# DW1000.net
KiCad netlist of a schematic drawn in Altium Designer
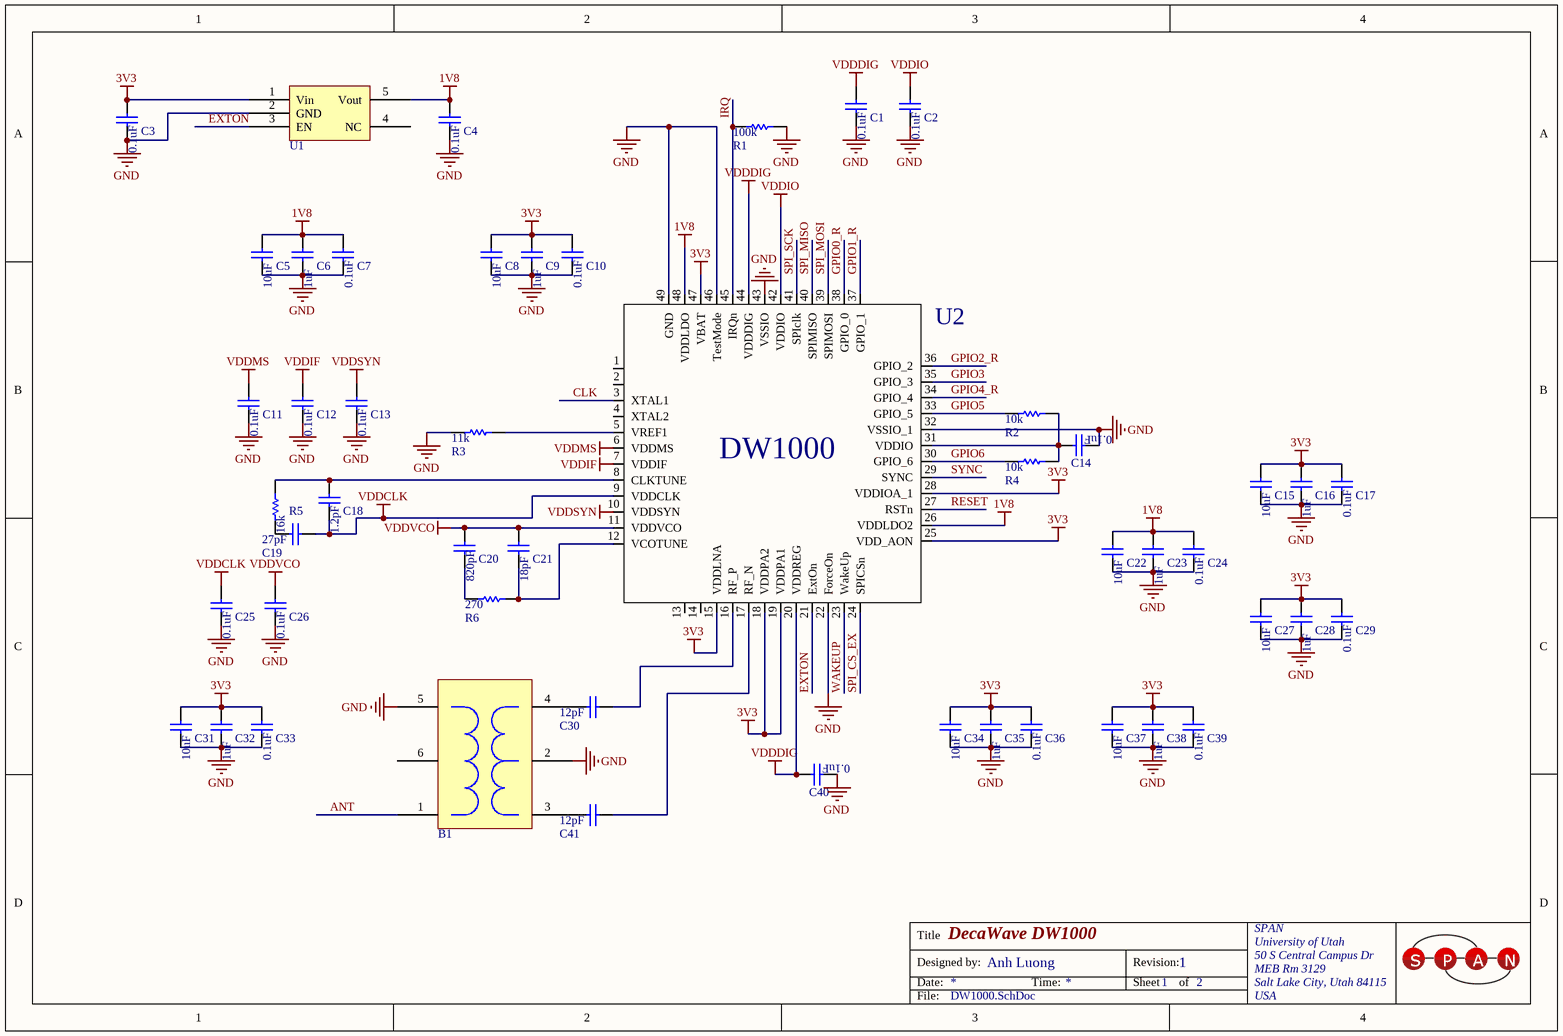
[diagram p0: DW1000.SchDoc]

(export (version "E")
  (design (tool "Eeschema 10.0.6"))
  (components
    (comp (ref "B1")
      (value "HHM1595A1")
      (footprint "BALUN")
      (description "XFMR BALUN RF 3.0-8.0GHZ UWB SMD")
      (fields (field (name "MANUFACTURER") "TDK Corporation"))
      (libsource (lib "DW1000Breakout") (part "HHM1595A1"))
    )
    (comp (ref "C1")
      (value "GRM188R71C104KA01D")
      (footprint "CAPC1608X08N (0603)")
      (description "CAP CER 0.1UF 16V 10% X7R 0603")
      (fields
        (field (name "MANUFACTURER") "Murata Electronics North America")
        (field (name "TOLERANCE") "±10%")
      )
      (libsource (lib "DW1000Breakout") (part "GRM188R71C104KA01D"))
    )
    (comp (ref "C2")
      (value "GRM188R71C104KA01D")
      (footprint "CAPC1608X08N (0603)")
      (description "CAP CER 0.1UF 16V 10% X7R 0603")
      (fields
        (field (name "MANUFACTURER") "Murata Electronics North America")
        (field (name "TOLERANCE") "±10%")
      )
      (libsource (lib "DW1000Breakout") (part "GRM188R71C104KA01D"))
    )
    (comp (ref "C3")
      (value "GRM188R71C104KA01D")
      (footprint "CAPC1608X08N (0603)")
      (description "CAP CER 0.1UF 16V 10% X7R 0603")
      (fields
        (field (name "MANUFACTURER") "Murata Electronics North America")
        (field (name "TOLERANCE") "±10%")
      )
      (libsource (lib "DW1000Breakout") (part "GRM188R71C104KA01D"))
    )
    (comp (ref "C4")
      (value "GRM188R71C104KA01D")
      (footprint "CAPC1608X08N (0603)")
      (description "CAP CER 0.1UF 16V 10% X7R 0603")
      (fields
        (field (name "MANUFACTURER") "Murata Electronics North America")
        (field (name "TOLERANCE") "±10%")
      )
      (libsource (lib "DW1000Breakout") (part "GRM188R71C104KA01D"))
    )
    (comp (ref "C5")
      (value "GRM188R60J106ME47D")
      (footprint "CAPC1608X08N (0603)")
      (description "CAP CER 10UF 6.3V 20% X5R 0603")
      (fields
        (field (name "MANUFACTURER") "Murata Electronics North America")
        (field (name "TOLERANCE") "±20%")
      )
      (libsource (lib "DWM1000Breakout") (part "GRM188R60J106ME47D"))
    )
    (comp (ref "C6")
      (value "GRM188R61A105KA61D")
      (footprint "CAPC1608X08N (0603)")
      (description "CAP CER 1UF 10V 10% X5R 0603")
      (fields
        (field (name "MANUFACTURER") "Murata Electronics North America")
        (field (name "TOLERANCE") "±10%")
      )
      (libsource (lib "DWM1000Breakout") (part "GRM188R61A105KA61D"))
    )
    (comp (ref "C7")
      (value "GRM188R71C104KA01D")
      (footprint "CAPC1608X08N (0603)")
      (description "CAP CER 0.1UF 16V 10% X7R 0603")
      (fields
        (field (name "MANUFACTURER") "Murata Electronics North America")
        (field (name "TOLERANCE") "±10%")
      )
      (libsource (lib "DWM1000Breakout") (part "GRM188R71C104KA01D"))
    )
    (comp (ref "C8")
      (value "GRM188R60J106ME47D")
      (footprint "CAPC1608X08N (0603)")
      (description "CAP CER 10UF 6.3V 20% X5R 0603")
      (fields
        (field (name "MANUFACTURER") "Murata Electronics North America")
        (field (name "TOLERANCE") "±20%")
      )
      (libsource (lib "DWM1000Breakout") (part "GRM188R60J106ME47D"))
    )
    (comp (ref "C9")
      (value "GRM188R61A105KA61D")
      (footprint "CAPC1608X08N (0603)")
      (description "CAP CER 1UF 10V 10% X5R 0603")
      (fields
        (field (name "MANUFACTURER") "Murata Electronics North America")
        (field (name "TOLERANCE") "±10%")
      )
      (libsource (lib "DWM1000Breakout") (part "GRM188R61A105KA61D"))
    )
    (comp (ref "C10")
      (value "GRM188R71C104KA01D")
      (footprint "CAPC1608X08N (0603)")
      (description "CAP CER 0.1UF 16V 10% X7R 0603")
      (fields
        (field (name "MANUFACTURER") "Murata Electronics North America")
        (field (name "TOLERANCE") "±10%")
      )
      (libsource (lib "DWM1000Breakout") (part "GRM188R71C104KA01D"))
    )
    (comp (ref "C11")
      (value "GRM188R71C104KA01D")
      (footprint "CAPC1608X08N (0603)")
      (description "CAP CER 0.1UF 16V 10% X7R 0603")
      (fields
        (field (name "MANUFACTURER") "Murata Electronics North America")
        (field (name "TOLERANCE") "±10%")
      )
      (libsource (lib "DW1000Breakout") (part "GRM188R71C104KA01D"))
    )
    (comp (ref "C12")
      (value "GRM188R71C104KA01D")
      (footprint "CAPC1608X08N (0603)")
      (description "CAP CER 0.1UF 16V 10% X7R 0603")
      (fields
        (field (name "MANUFACTURER") "Murata Electronics North America")
        (field (name "TOLERANCE") "±10%")
      )
      (libsource (lib "DW1000Breakout") (part "GRM188R71C104KA01D"))
    )
    (comp (ref "C13")
      (value "GRM188R71C104KA01D")
      (footprint "CAPC1608X08N (0603)")
      (description "CAP CER 0.1UF 16V 10% X7R 0603")
      (fields
        (field (name "MANUFACTURER") "Murata Electronics North America")
        (field (name "TOLERANCE") "±10%")
      )
      (libsource (lib "DW1000Breakout") (part "GRM188R71C104KA01D"))
    )
    (comp (ref "C14")
      (value "GRM188R71C104KA01D")
      (footprint "CAPC1608X08N (0603)")
      (description "CAP CER 0.1UF 16V 10% X7R 0603")
      (fields
        (field (name "MANUFACTURER") "Murata Electronics North America")
        (field (name "TOLERANCE") "±10%")
      )
      (libsource (lib "DW1000Breakout") (part "GRM188R71C104KA01D"))
    )
    (comp (ref "C15")
      (value "GRM188R60J106ME47D")
      (footprint "CAPC1608X08N (0603)")
      (description "CAP CER 10UF 6.3V 20% X5R 0603")
      (fields
        (field (name "MANUFACTURER") "Murata Electronics North America")
        (field (name "TOLERANCE") "±20%")
      )
      (libsource (lib "DWM1000Breakout") (part "GRM188R60J106ME47D"))
    )
    (comp (ref "C16")
      (value "GRM188R61A105KA61D")
      (footprint "CAPC1608X08N (0603)")
      (description "CAP CER 1UF 10V 10% X5R 0603")
      (fields
        (field (name "MANUFACTURER") "Murata Electronics North America")
        (field (name "TOLERANCE") "±10%")
      )
      (libsource (lib "DWM1000Breakout") (part "GRM188R61A105KA61D"))
    )
    (comp (ref "C17")
      (value "GRM188R71C104KA01D")
      (footprint "CAPC1608X08N (0603)")
      (description "CAP CER 0.1UF 16V 10% X7R 0603")
      (fields
        (field (name "MANUFACTURER") "Murata Electronics North America")
        (field (name "TOLERANCE") "±10%")
      )
      (libsource (lib "DWM1000Breakout") (part "GRM188R71C104KA01D"))
    )
    (comp (ref "C18")
      (value "GRM1885C1H1R2CA01D")
      (footprint "CAPC1608X08N (0603)")
      (description "CAP CER 1.2PF 50V NP0 0603")
      (fields
        (field (name "MANUFACTURER") "Murata Electronics North America")
        (field (name "TOLERANCE") "±0.25pF")
      )
      (libsource (lib "DW1000Breakout") (part "GRM1885C1H1R2CA01D"))
    )
    (comp (ref "C19")
      (value "GRM1885C1H270JA01D")
      (footprint "CAPC1608X08N (0603)")
      (description "CAP CER 27PF 50V NP0 0603")
      (fields
        (field (name "MANUFACTURER") "Murata Electronics North America")
        (field (name "TOLERANCE") "±5%")
      )
      (libsource (lib "DW1000Breakout") (part "GRM1885C1H270JA01D"))
    )
    (comp (ref "C20")
      (value "GRM188R71H821KA01D")
      (footprint "CAPC1608X08N (0603)")
      (description "CAP CER 820PF 50V X7R 0603")
      (fields
        (field (name "MANUFACTURER") "Murata Electronics North America")
        (field (name "TOLERANCE") "±10%")
      )
      (libsource (lib "DW1000Breakout") (part "GRM188R71H821KA01D"))
    )
    (comp (ref "C21")
      (value "GRM1885C1H180JA01D")
      (footprint "CAPC1608X08N (0603)")
      (description "CAP CER 18PF 50V NP0 0603")
      (fields
        (field (name "MANUFACTURER") "Murata Electronics North America")
        (field (name "TOLERANCE") "±5%")
      )
      (libsource (lib "DW1000Breakout") (part "GRM1885C1H180JA01D"))
    )
    (comp (ref "C22")
      (value "GRM188R60J106ME47D")
      (footprint "CAPC1608X08N (0603)")
      (description "CAP CER 10UF 6.3V 20% X5R 0603")
      (fields
        (field (name "MANUFACTURER") "Murata Electronics North America")
        (field (name "TOLERANCE") "±20%")
      )
      (libsource (lib "DWM1000Breakout") (part "GRM188R60J106ME47D"))
    )
    (comp (ref "C23")
      (value "GRM188R61A105KA61D")
      (footprint "CAPC1608X08N (0603)")
      (description "CAP CER 1UF 10V 10% X5R 0603")
      (fields
        (field (name "MANUFACTURER") "Murata Electronics North America")
        (field (name "TOLERANCE") "±10%")
      )
      (libsource (lib "DWM1000Breakout") (part "GRM188R61A105KA61D"))
    )
    (comp (ref "C24")
      (value "GRM188R71C104KA01D")
      (footprint "CAPC1608X08N (0603)")
      (description "CAP CER 0.1UF 16V 10% X7R 0603")
      (fields
        (field (name "MANUFACTURER") "Murata Electronics North America")
        (field (name "TOLERANCE") "±10%")
      )
      (libsource (lib "DWM1000Breakout") (part "GRM188R71C104KA01D"))
    )
    (comp (ref "C25")
      (value "GRM188R71C104KA01D")
      (footprint "CAPC1608X08N (0603)")
      (description "CAP CER 0.1UF 16V 10% X7R 0603")
      (fields
        (field (name "MANUFACTURER") "Murata Electronics North America")
        (field (name "TOLERANCE") "±10%")
      )
      (libsource (lib "DWM1000Breakout") (part "GRM188R71C104KA01D"))
    )
    (comp (ref "C26")
      (value "GRM188R71C104KA01D")
      (footprint "CAPC1608X08N (0603)")
      (description "CAP CER 0.1UF 16V 10% X7R 0603")
      (fields
        (field (name "MANUFACTURER") "Murata Electronics North America")
        (field (name "TOLERANCE") "±10%")
      )
      (libsource (lib "DWM1000Breakout") (part "GRM188R71C104KA01D"))
    )
    (comp (ref "C27")
      (value "GRM188R60J106ME47D")
      (footprint "CAPC1608X08N (0603)")
      (description "CAP CER 10UF 6.3V 20% X5R 0603")
      (fields
        (field (name "MANUFACTURER") "Murata Electronics North America")
        (field (name "TOLERANCE") "±20%")
      )
      (libsource (lib "DWM1000Breakout") (part "GRM188R60J106ME47D"))
    )
    (comp (ref "C28")
      (value "GRM188R61A105KA61D")
      (footprint "CAPC1608X08N (0603)")
      (description "CAP CER 1UF 10V 10% X5R 0603")
      (fields
        (field (name "MANUFACTURER") "Murata Electronics North America")
        (field (name "TOLERANCE") "±10%")
      )
      (libsource (lib "DWM1000Breakout") (part "GRM188R61A105KA61D"))
    )
    (comp (ref "C29")
      (value "GRM188R71C104KA01D")
      (footprint "CAPC1608X08N (0603)")
      (description "CAP CER 0.1UF 16V 10% X7R 0603")
      (fields
        (field (name "MANUFACTURER") "Murata Electronics North America")
        (field (name "TOLERANCE") "±10%")
      )
      (libsource (lib "DWM1000Breakout") (part "GRM188R71C104KA01D"))
    )
    (comp (ref "C30")
      (value "GRM1885C1H120JA01D")
      (footprint "CAPC1608X08N (0603)")
      (description "CAP CER 12PF 50V NP0 0603")
      (fields
        (field (name "MANUFACTURER") "Murata Electronics North America")
        (field (name "TOLERANCE") "±5%")
      )
      (libsource (lib "DW1000Breakout") (part "GRM1885C1H120JA01D"))
    )
    (comp (ref "C31")
      (value "GRM188R60J106ME47D")
      (footprint "CAPC1608X08N (0603)")
      (description "CAP CER 10UF 6.3V 20% X5R 0603")
      (fields
        (field (name "MANUFACTURER") "Murata Electronics North America")
        (field (name "TOLERANCE") "±20%")
      )
      (libsource (lib "DWM1000Breakout") (part "GRM188R60J106ME47D"))
    )
    (comp (ref "C32")
      (value "GRM188R61A105KA61D")
      (footprint "CAPC1608X08N (0603)")
      (description "CAP CER 1UF 10V 10% X5R 0603")
      (fields
        (field (name "MANUFACTURER") "Murata Electronics North America")
        (field (name "TOLERANCE") "±10%")
      )
      (libsource (lib "DWM1000Breakout") (part "GRM188R61A105KA61D"))
    )
    (comp (ref "C33")
      (value "GRM188R71C104KA01D")
      (footprint "CAPC1608X08N (0603)")
      (description "CAP CER 0.1UF 16V 10% X7R 0603")
      (fields
        (field (name "MANUFACTURER") "Murata Electronics North America")
        (field (name "TOLERANCE") "±10%")
      )
      (libsource (lib "DWM1000Breakout") (part "GRM188R71C104KA01D"))
    )
    (comp (ref "C34")
      (value "GRM188R60J106ME47D")
      (footprint "CAPC1608X08N (0603)")
      (description "CAP CER 10UF 6.3V 20% X5R 0603")
      (fields
        (field (name "MANUFACTURER") "Murata Electronics North America")
        (field (name "TOLERANCE") "±20%")
      )
      (libsource (lib "DWM1000Breakout") (part "GRM188R60J106ME47D"))
    )
    (comp (ref "C35")
      (value "GRM188R61A105KA61D")
      (footprint "CAPC1608X08N (0603)")
      (description "CAP CER 1UF 10V 10% X5R 0603")
      (fields
        (field (name "MANUFACTURER") "Murata Electronics North America")
        (field (name "TOLERANCE") "±10%")
      )
      (libsource (lib "DWM1000Breakout") (part "GRM188R61A105KA61D"))
    )
    (comp (ref "C36")
      (value "GRM188R71C104KA01D")
      (footprint "CAPC1608X08N (0603)")
      (description "CAP CER 0.1UF 16V 10% X7R 0603")
      (fields
        (field (name "MANUFACTURER") "Murata Electronics North America")
        (field (name "TOLERANCE") "±10%")
      )
      (libsource (lib "DWM1000Breakout") (part "GRM188R71C104KA01D"))
    )
    (comp (ref "C37")
      (value "GRM188R60J106ME47D")
      (footprint "CAPC1608X08N (0603)")
      (description "CAP CER 10UF 6.3V 20% X5R 0603")
      (fields
        (field (name "MANUFACTURER") "Murata Electronics North America")
        (field (name "TOLERANCE") "±20%")
      )
      (libsource (lib "DWM1000Breakout") (part "GRM188R60J106ME47D"))
    )
    (comp (ref "C38")
      (value "GRM188R61A105KA61D")
      (footprint "CAPC1608X08N (0603)")
      (description "CAP CER 1UF 10V 10% X5R 0603")
      (fields
        (field (name "MANUFACTURER") "Murata Electronics North America")
        (field (name "TOLERANCE") "±10%")
      )
      (libsource (lib "DWM1000Breakout") (part "GRM188R61A105KA61D"))
    )
    (comp (ref "C39")
      (value "GRM188R71C104KA01D")
      (footprint "CAPC1608X08N (0603)")
      (description "CAP CER 0.1UF 16V 10% X7R 0603")
      (fields
        (field (name "MANUFACTURER") "Murata Electronics North America")
        (field (name "TOLERANCE") "±10%")
      )
      (libsource (lib "DWM1000Breakout") (part "GRM188R71C104KA01D"))
    )
    (comp (ref "C40")
      (value "GRM188R71C104KA01D")
      (footprint "CAPC1608X08N (0603)")
      (description "CAP CER 0.1UF 16V 10% X7R 0603")
      (fields
        (field (name "MANUFACTURER") "Murata Electronics North America")
        (field (name "TOLERANCE") "±10%")
      )
      (libsource (lib "DW1000Breakout") (part "GRM188R71C104KA01D"))
    )
    (comp (ref "C41")
      (value "GRM1885C1H120JA01D")
      (footprint "CAPC1608X08N (0603)")
      (description "CAP CER 12PF 50V NP0 0603")
      (fields
        (field (name "MANUFACTURER") "Murata Electronics North America")
        (field (name "TOLERANCE") "±5%")
      )
      (libsource (lib "DW1000Breakout") (part "GRM1885C1H120JA01D"))
    )
    (comp (ref "R1")
      (value "MCR03ERTJ104")
      (footprint "RESC1608X06N (0603)")
      (description "RES SMD 100K OHM 5% 1/10W 0603")
      (fields (field (name "MANUFACTURER") "Rohm Semiconductor") (field (name "TOLERANCE") "±5%"))
      (libsource (lib "DW1000Breakout") (part "MCR03ERTJ104"))
    )
    (comp (ref "R2")
      (value "MCR03ERTJ103")
      (footprint "RESC1608X06N (0603)")
      (description "RES 10K OHM 1/10W 5% 0603 SMD")
      (fields (field (name "MANUFACTURER") "Rohm Semiconductor") (field (name "TOLERANCE") "±5%"))
      (libsource (lib "DW1000Breakout") (part "MCR03ERTJ103"))
    )
    (comp (ref "R3")
      (value "MCR03ERTJ113")
      (footprint "RESC1608X06N (0603)")
      (description "RES SMD 11K OHM 5% 1/10W 0603")
      (fields (field (name "MANUFACTURER") "Rohm Semiconductor") (field (name "TOLERANCE") "±5%"))
      (libsource (lib "DW1000Breakout") (part "MCR03ERTJ113"))
    )
    (comp (ref "R4")
      (value "MCR03ERTJ103")
      (footprint "RESC1608X06N (0603)")
      (description "RES 10K OHM 1/10W 5% 0603 SMD")
      (fields (field (name "MANUFACTURER") "Rohm Semiconductor") (field (name "TOLERANCE") "±5%"))
      (libsource (lib "DW1000Breakout") (part "MCR03ERTJ103"))
    )
    (comp (ref "R5")
      (value "MCR03ERTJ163")
      (footprint "RESC1608X06N (0603)")
      (description "RES SMD 16K OHM 5% 1/10W 0603")
      (fields (field (name "MANUFACTURER") "Rohm Semiconductor") (field (name "TOLERANCE") "±5%"))
      (libsource (lib "DW1000Breakout") (part "MCR03ERTJ163"))
    )
    (comp (ref "R6")
      (value "MCR03ERTJ271")
      (footprint "RESC1608X06N (0603)")
      (description "RES SMD 270 OHM 5% 1/10W 0603")
      (fields (field (name "MANUFACTURER") "Rohm Semiconductor") (field (name "TOLERANCE") "±5%"))
      (libsource (lib "DW1000Breakout") (part "MCR03ERTJ271"))
    )
    (comp (ref "U1")
      (value "LP5907MFX-1.8/NOPB")
      (footprint "SOT95P280X145-5N")
      (description "IC REG LDO 1.8V 0.25A SOT23-5")
      (fields (field (name "MANUFACTURER") "Texas Instruments"))
      (libsource (lib "DW1000Breakout") (part "LP5907MFX-1.8/NOPB"))
    )
    (comp (ref "U2")
      (value "DW1000 IC")
      (footprint "QFN-48")
      (description "UWB DW1000")
      (fields (field (name "PART NUMBER") "DW1000_QFN") (field (name "MANUFACTURER") "Decawave Ltd."))
      (libsource (lib "DW1000") (part "DW1000_QFN_48"))
    )
  )
  (nets
    (net (code "1") (name "/ANT") (class "Default")
      (node (ref "B1") (pin "1") (pinfunction "1_1") (pintype "passive"))
    )
    (net (code "2") (name "/CLK") (class "Default")
      (node (ref "U2") (pin "3") (pinfunction "XTAL1_3") (pintype "passive"))
    )
    (net (code "3") (name "/EXTON") (class "Default")
      (node (ref "U1") (pin "3") (pinfunction "EN_3") (pintype "passive"))
      (node (ref "U2") (pin "21") (pinfunction "ExtOn_21") (pintype "passive"))
    )
    (net (code "4") (name "/GPIO0_R") (class "Default")
      (node (ref "U2") (pin "38") (pinfunction "GPIO_0_38") (pintype "passive"))
    )
    (net (code "5") (name "/GPIO1_R") (class "Default")
      (node (ref "U2") (pin "37") (pinfunction "GPIO_1_37") (pintype "passive"))
    )
    (net (code "6") (name "/GPIO2_R") (class "Default")
      (node (ref "U2") (pin "36") (pinfunction "GPIO_2_36") (pintype "passive"))
    )
    (net (code "7") (name "/GPIO3") (class "Default")
      (node (ref "U2") (pin "35") (pinfunction "GPIO_3_35") (pintype "passive"))
    )
    (net (code "8") (name "/GPIO4_R") (class "Default")
      (node (ref "U2") (pin "34") (pinfunction "GPIO_4_34") (pintype "passive"))
    )
    (net (code "9") (name "/GPIO5") (class "Default")
      (node (ref "R2") (pin "1") (pinfunction "1_1") (pintype "passive"))
      (node (ref "U2") (pin "33") (pinfunction "GPIO_5_33") (pintype "passive"))
    )
    (net (code "10") (name "/GPIO6") (class "Default")
      (node (ref "R4") (pin "1") (pinfunction "1_1") (pintype "passive"))
      (node (ref "U2") (pin "30") (pinfunction "GPIO_6_30") (pintype "passive"))
    )
    (net (code "11") (name "/IRQ") (class "Default")
      (node (ref "R1") (pin "1") (pinfunction "1_1") (pintype "passive"))
      (node (ref "U2") (pin "45") (pinfunction "IRQn_45") (pintype "passive"))
    )
    (net (code "12") (name "/RESET") (class "Default")
      (node (ref "U2") (pin "27") (pinfunction "RSTn_27") (pintype "passive"))
    )
    (net (code "13") (name "/SPI_CS_EX") (class "Default")
      (node (ref "U2") (pin "24") (pinfunction "SPICSn_24") (pintype "passive"))
    )
    (net (code "14") (name "/SPI_MISO") (class "Default")
      (node (ref "U2") (pin "40") (pinfunction "SPIMISO_40") (pintype "passive"))
    )
    (net (code "15") (name "/SPI_MOSI") (class "Default")
      (node (ref "U2") (pin "39") (pinfunction "SPIMOSI_39") (pintype "passive"))
    )
    (net (code "16") (name "/SPI_SCK") (class "Default")
      (node (ref "U2") (pin "41") (pinfunction "SPIclk_41") (pintype "passive"))
    )
    (net (code "17") (name "/SYNC") (class "Default")
      (node (ref "U2") (pin "29") (pinfunction "SYNC_29") (pintype "passive"))
    )
    (net (code "18") (name "/WAKEUP") (class "Default")
      (node (ref "U2") (pin "23") (pinfunction "WakeUp_23") (pintype "passive"))
    )
    (net (code "19") (name "1V8") (class "Default")
      (node (ref "C22") (pin "2") (pinfunction "2_2") (pintype "passive"))
      (node (ref "C23") (pin "2") (pinfunction "2_2") (pintype "passive"))
      (node (ref "C24") (pin "2") (pinfunction "2_2") (pintype "passive"))
      (node (ref "C4") (pin "2") (pinfunction "2_2") (pintype "passive"))
      (node (ref "C5") (pin "2") (pinfunction "2_2") (pintype "passive"))
      (node (ref "C6") (pin "2") (pinfunction "2_2") (pintype "passive"))
      (node (ref "C7") (pin "2") (pinfunction "2_2") (pintype "passive"))
      (node (ref "U1") (pin "5") (pinfunction "Vout_5") (pintype "passive"))
      (node (ref "U2") (pin "26") (pinfunction "VDDLDO2_26") (pintype "passive"))
      (node (ref "U2") (pin "48") (pinfunction "VDDLDO_48") (pintype "passive"))
    )
    (net (code "20") (name "3V3") (class "Default")
      (node (ref "C10") (pin "2") (pinfunction "2_2") (pintype "passive"))
      (node (ref "C15") (pin "2") (pinfunction "2_2") (pintype "passive"))
      (node (ref "C16") (pin "2") (pinfunction "2_2") (pintype "passive"))
      (node (ref "C17") (pin "2") (pinfunction "2_2") (pintype "passive"))
      (node (ref "C27") (pin "2") (pinfunction "2_2") (pintype "passive"))
      (node (ref "C28") (pin "2") (pinfunction "2_2") (pintype "passive"))
      (node (ref "C29") (pin "2") (pinfunction "2_2") (pintype "passive"))
      (node (ref "C3") (pin "2") (pinfunction "2_2") (pintype "passive"))
      (node (ref "C31") (pin "2") (pinfunction "2_2") (pintype "passive"))
      (node (ref "C32") (pin "2") (pinfunction "2_2") (pintype "passive"))
      (node (ref "C33") (pin "2") (pinfunction "2_2") (pintype "passive"))
      (node (ref "C34") (pin "2") (pinfunction "2_2") (pintype "passive"))
      (node (ref "C35") (pin "2") (pinfunction "2_2") (pintype "passive"))
      (node (ref "C36") (pin "2") (pinfunction "2_2") (pintype "passive"))
      (node (ref "C37") (pin "2") (pinfunction "2_2") (pintype "passive"))
      (node (ref "C38") (pin "2") (pinfunction "2_2") (pintype "passive"))
      (node (ref "C39") (pin "2") (pinfunction "2_2") (pintype "passive"))
      (node (ref "C8") (pin "2") (pinfunction "2_2") (pintype "passive"))
      (node (ref "C9") (pin "2") (pinfunction "2_2") (pintype "passive"))
      (node (ref "U1") (pin "1") (pinfunction "Vin_1") (pintype "passive"))
      (node (ref "U2") (pin "15") (pinfunction "VDDLNA_15") (pintype "passive"))
      (node (ref "U2") (pin "18") (pinfunction "VDDPA2_18") (pintype "passive"))
      (node (ref "U2") (pin "19") (pinfunction "VDDPA1_19") (pintype "passive"))
      (node (ref "U2") (pin "25") (pinfunction "VDD_AON_25") (pintype "passive"))
      (node (ref "U2") (pin "28") (pinfunction "VDDIOA_1_28") (pintype "passive"))
      (node (ref "U2") (pin "47") (pinfunction "VBAT_47") (pintype "passive"))
    )
    (net (code "21") (name "GND") (class "Default")
      (node (ref "B1") (pin "2") (pinfunction "2_2") (pintype "passive"))
      (node (ref "B1") (pin "5") (pinfunction "5_5") (pintype "passive"))
      (node (ref "C1") (pin "1") (pinfunction "1_1") (pintype "passive"))
      (node (ref "C10") (pin "1") (pinfunction "1_1") (pintype "passive"))
      (node (ref "C11") (pin "1") (pinfunction "1_1") (pintype "passive"))
      (node (ref "C12") (pin "1") (pinfunction "1_1") (pintype "passive"))
      (node (ref "C13") (pin "1") (pinfunction "1_1") (pintype "passive"))
      (node (ref "C14") (pin "1") (pinfunction "1_1") (pintype "passive"))
      (node (ref "C15") (pin "1") (pinfunction "1_1") (pintype "passive"))
      (node (ref "C16") (pin "1") (pinfunction "1_1") (pintype "passive"))
      (node (ref "C17") (pin "1") (pinfunction "1_1") (pintype "passive"))
      (node (ref "C2") (pin "1") (pinfunction "1_1") (pintype "passive"))
      (node (ref "C22") (pin "1") (pinfunction "1_1") (pintype "passive"))
      (node (ref "C23") (pin "1") (pinfunction "1_1") (pintype "passive"))
      (node (ref "C24") (pin "1") (pinfunction "1_1") (pintype "passive"))
      (node (ref "C25") (pin "1") (pinfunction "1_1") (pintype "passive"))
      (node (ref "C26") (pin "1") (pinfunction "1_1") (pintype "passive"))
      (node (ref "C27") (pin "1") (pinfunction "1_1") (pintype "passive"))
      (node (ref "C28") (pin "1") (pinfunction "1_1") (pintype "passive"))
      (node (ref "C29") (pin "1") (pinfunction "1_1") (pintype "passive"))
      (node (ref "C3") (pin "1") (pinfunction "1_1") (pintype "passive"))
      (node (ref "C31") (pin "1") (pinfunction "1_1") (pintype "passive"))
      (node (ref "C32") (pin "1") (pinfunction "1_1") (pintype "passive"))
      (node (ref "C33") (pin "1") (pinfunction "1_1") (pintype "passive"))
      (node (ref "C34") (pin "1") (pinfunction "1_1") (pintype "passive"))
      (node (ref "C35") (pin "1") (pinfunction "1_1") (pintype "passive"))
      (node (ref "C36") (pin "1") (pinfunction "1_1") (pintype "passive"))
      (node (ref "C37") (pin "1") (pinfunction "1_1") (pintype "passive"))
      (node (ref "C38") (pin "1") (pinfunction "1_1") (pintype "passive"))
      (node (ref "C39") (pin "1") (pinfunction "1_1") (pintype "passive"))
      (node (ref "C4") (pin "1") (pinfunction "1_1") (pintype "passive"))
      (node (ref "C40") (pin "1") (pinfunction "1_1") (pintype "passive"))
      (node (ref "C5") (pin "1") (pinfunction "1_1") (pintype "passive"))
      (node (ref "C6") (pin "1") (pinfunction "1_1") (pintype "passive"))
      (node (ref "C7") (pin "1") (pinfunction "1_1") (pintype "passive"))
      (node (ref "C8") (pin "1") (pinfunction "1_1") (pintype "passive"))
      (node (ref "C9") (pin "1") (pinfunction "1_1") (pintype "passive"))
      (node (ref "R1") (pin "2") (pinfunction "2_2") (pintype "passive"))
      (node (ref "R3") (pin "1") (pinfunction "1_1") (pintype "passive"))
      (node (ref "U1") (pin "2") (pinfunction "GND_2") (pintype "passive"))
      (node (ref "U2") (pin "22") (pinfunction "ForceOn_22") (pintype "passive"))
      (node (ref "U2") (pin "32") (pinfunction "VSSIO_1_32") (pintype "passive"))
      (node (ref "U2") (pin "43") (pinfunction "VSSIO_43") (pintype "passive"))
      (node (ref "U2") (pin "46") (pinfunction "TestMode_46") (pintype "passive"))
      (node (ref "U2") (pin "49") (pinfunction "GND_49") (pintype "passive"))
    )
    (net (code "22") (name "Net-(B1-Pad3)") (class "Default")
      (node (ref "B1") (pin "3") (pinfunction "3_3") (pintype "passive"))
      (node (ref "C41") (pin "1") (pinfunction "1_1") (pintype "passive"))
    )
    (net (code "23") (name "Net-(B1-Pad4)") (class "Default")
      (node (ref "B1") (pin "4") (pinfunction "4_4") (pintype "passive"))
      (node (ref "C30") (pin "1") (pinfunction "1_1") (pintype "passive"))
    )
    (net (code "24") (name "Net-(C14-Pad2)") (class "Default")
      (node (ref "C14") (pin "2") (pinfunction "2_2") (pintype "passive"))
      (node (ref "R2") (pin "2") (pinfunction "2_2") (pintype "passive"))
      (node (ref "R4") (pin "2") (pinfunction "2_2") (pintype "passive"))
      (node (ref "U2") (pin "31") (pinfunction "VDDIO_31") (pintype "passive"))
    )
    (net (code "25") (name "Net-(C19-Pad1)") (class "Default")
      (node (ref "C19") (pin "1") (pinfunction "1_1") (pintype "passive"))
      (node (ref "R5") (pin "1") (pinfunction "1_1") (pintype "passive"))
    )
    (net (code "26") (name "Net-(C20-Pad1)") (class "Default")
      (node (ref "C20") (pin "1") (pinfunction "1_1") (pintype "passive"))
      (node (ref "R6") (pin "1") (pinfunction "1_1") (pintype "passive"))
    )
    (net (code "27") (name "Net-(U2-CLKTUNE)") (class "Default")
      (node (ref "C18") (pin "2") (pinfunction "2_2") (pintype "passive"))
      (node (ref "R5") (pin "2") (pinfunction "2_2") (pintype "passive"))
      (node (ref "U2") (pin "8") (pinfunction "CLKTUNE_8") (pintype "passive"))
    )
    (net (code "28") (name "Net-(U2-RF_N)") (class "Default")
      (node (ref "C41") (pin "2") (pinfunction "2_2") (pintype "passive"))
      (node (ref "U2") (pin "17") (pinfunction "RF_N_17") (pintype "passive"))
    )
    (net (code "29") (name "Net-(U2-RF_P)") (class "Default")
      (node (ref "C30") (pin "2") (pinfunction "2_2") (pintype "passive"))
      (node (ref "U2") (pin "16") (pinfunction "RF_P_16") (pintype "passive"))
    )
    (net (code "30") (name "Net-(U2-VCOTUNE)") (class "Default")
      (node (ref "C21") (pin "1") (pinfunction "1_1") (pintype "passive"))
      (node (ref "R6") (pin "2") (pinfunction "2_2") (pintype "passive"))
      (node (ref "U2") (pin "12") (pinfunction "VCOTUNE_12") (pintype "passive"))
    )
    (net (code "31") (name "Net-(U2-VREF1)") (class "Default")
      (node (ref "R3") (pin "2") (pinfunction "2_2") (pintype "passive"))
      (node (ref "U2") (pin "5") (pinfunction "VREF1_5") (pintype "passive"))
    )
    (net (code "32") (name "VDDCLK") (class "Default")
      (node (ref "C18") (pin "1") (pinfunction "1_1") (pintype "passive"))
      (node (ref "C19") (pin "2") (pinfunction "2_2") (pintype "passive"))
      (node (ref "C25") (pin "2") (pinfunction "2_2") (pintype "passive"))
      (node (ref "U2") (pin "9") (pinfunction "VDDCLK_9") (pintype "passive"))
    )
    (net (code "33") (name "VDDDIG") (class "Default")
      (node (ref "C1") (pin "2") (pinfunction "2_2") (pintype "passive"))
      (node (ref "C40") (pin "2") (pinfunction "2_2") (pintype "passive"))
      (node (ref "U2") (pin "20") (pinfunction "VDDREG_20") (pintype "passive"))
      (node (ref "U2") (pin "44") (pinfunction "VDDDIG_44") (pintype "passive"))
    )
    (net (code "34") (name "VDDIF") (class "Default")
      (node (ref "C12") (pin "2") (pinfunction "2_2") (pintype "passive"))
      (node (ref "U2") (pin "7") (pinfunction "VDDIF_7") (pintype "passive"))
    )
    (net (code "35") (name "VDDIO") (class "Default")
      (node (ref "C2") (pin "2") (pinfunction "2_2") (pintype "passive"))
      (node (ref "U2") (pin "42") (pinfunction "VDDIO_42") (pintype "passive"))
    )
    (net (code "36") (name "VDDMS") (class "Default")
      (node (ref "C11") (pin "2") (pinfunction "2_2") (pintype "passive"))
      (node (ref "U2") (pin "6") (pinfunction "VDDMS_6") (pintype "passive"))
    )
    (net (code "37") (name "VDDSYN") (class "Default")
      (node (ref "C13") (pin "2") (pinfunction "2_2") (pintype "passive"))
      (node (ref "U2") (pin "10") (pinfunction "VDDSYN_10") (pintype "passive"))
    )
    (net (code "38") (name "VDDVCO") (class "Default")
      (node (ref "C20") (pin "2") (pinfunction "2_2") (pintype "passive"))
      (node (ref "C21") (pin "2") (pinfunction "2_2") (pintype "passive"))
      (node (ref "C26") (pin "2") (pinfunction "2_2") (pintype "passive"))
      (node (ref "U2") (pin "11") (pinfunction "VDDVCO_11") (pintype "passive"))
    )
    (net (code "39") (name "unconnected-(B1-Pad6)") (class "Default")
      (node (ref "B1") (pin "6") (pinfunction "6_6") (pintype "passive"))
    )
    (net (code "40") (name "unconnected-(U1-NC-Pad4)") (class "Default")
      (node (ref "U1") (pin "4") (pinfunction "NC_4") (pintype "passive"))
    )
    (net (code "41") (name "unconnected-(U2-Pad1)") (class "Default")
      (node (ref "U2") (pin "1") (pintype "passive"))
    )
    (net (code "42") (name "unconnected-(U2-Pad2)") (class "Default")
      (node (ref "U2") (pin "2") (pintype "passive"))
    )
    (net (code "43") (name "unconnected-(U2-Pad13)") (class "Default")
      (node (ref "U2") (pin "13") (pintype "passive"))
    )
    (net (code "44") (name "unconnected-(U2-Pad14)") (class "Default")
      (node (ref "U2") (pin "14") (pintype "passive"))
    )
    (net (code "45") (name "unconnected-(U2-XTAL2-Pad4)") (class "Default")
      (node (ref "U2") (pin "4") (pinfunction "XTAL2_4") (pintype "passive"))
    )
  )
)
